# AEMLION-R4.net
KiCad netlist of a schematic drawn in EAGLE
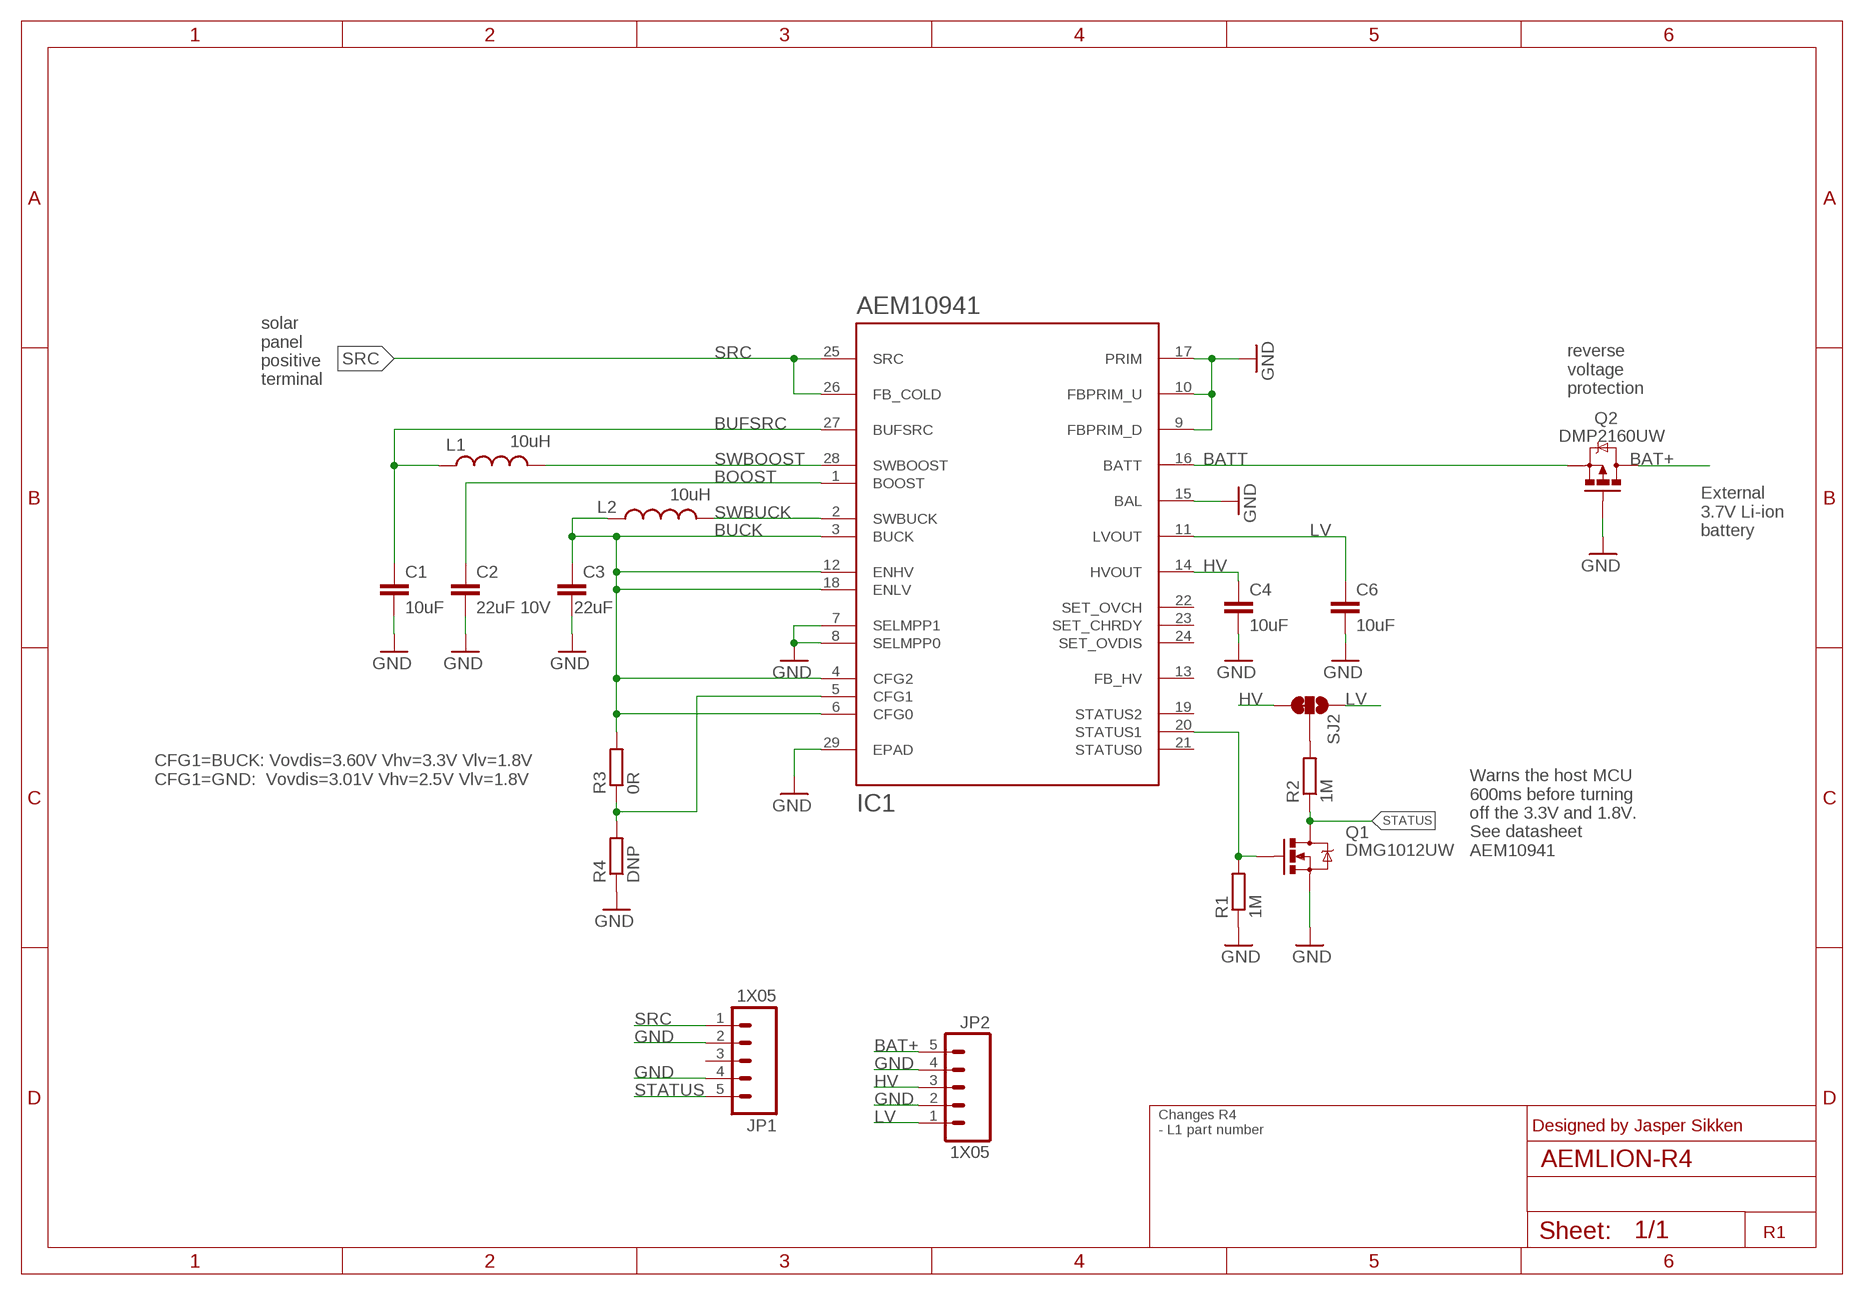
[diagram p0: schematic, sheet 1]

(export (version "E")
  (design (tool "Eeschema 10.0.6"))
  (components
    (comp (ref "C1")
      (value "10uF")
      (footprint "eagle-import:C0603")
      (fields
        (field (name "MF") "Taiyo Yuden")
        (field (name "MPN") "LMK107BBJ106MALT")
        (field (name "MF_1") "KEYSTONE")
        (field (name "MPN_1") "1049P")
      )
      (libsource (lib "eagle-import") (part "C0603_10UF"))
    )
    (comp (ref "C2")
      (value "22uF 10V")
      (footprint "eagle-import:C0603")
      (fields
        (field (name "MF") "Murata")
        (field (name "MPN") "GRM188R61A226ME15D")
        (field (name "MF_1") "TDK")
        (field (name "MPN_1") "CGA5L1X7S1A226M160AC")
      )
      (libsource (lib "eagle-import") (part "C0603_22UF"))
    )
    (comp (ref "C3")
      (value "22uF")
      (footprint "eagle-import:C0603")
      (fields
        (field (name "MF") "Taiyo Yuden")
        (field (name "MPN") "LMK107BBJ106MALT")
        (field (name "MF_1") "KEYSTONE")
        (field (name "MPN_1") "1049P")
      )
      (libsource (lib "eagle-import") (part "C0603_10UF"))
    )
    (comp (ref "C4")
      (value "10uF")
      (footprint "eagle-import:C0603")
      (fields
        (field (name "MF") "Taiyo Yuden")
        (field (name "MPN") "LMK107BBJ106MALT")
        (field (name "MF_1") "KEYSTONE")
        (field (name "MPN_1") "1049P")
      )
      (libsource (lib "eagle-import") (part "C0603_10UF"))
    )
    (comp (ref "C6")
      (value "10uF")
      (footprint "eagle-import:C0603")
      (fields
        (field (name "MF") "Taiyo Yuden")
        (field (name "MPN") "LMK107BBJ106MALT")
        (field (name "MF_1") "KEYSTONE")
        (field (name "MPN_1") "1049P")
      )
      (libsource (lib "eagle-import") (part "C0603_10UF"))
    )
    (comp (ref "IC1")
      (value "AEM10941")
      (footprint "eagle-import:QFN50P505X505X90-28")
      (fields (field (name "MF") "e-peas"))
      (libsource (lib "eagle-import") (part "AEM10941"))
    )
    (comp (ref "JP1")
      (value "1X05")
      (footprint "eagle-import:1X05_2.54MM_ROUND_NOSILK")
      (libsource (lib "eagle-import") (part "1X05"))
    )
    (comp (ref "JP2")
      (value "1X05")
      (footprint "eagle-import:1X05_2.54MM_ROUND_NOSILK")
      (libsource (lib "eagle-import") (part "1X05"))
    )
    (comp (ref "L1")
      (value "10uH")
      (footprint "eagle-import:L_3225MM")
      (fields (field (name "MF") "Murata") (field (name "MPN") "DFE322512F-100M=P2"))
      (libsource (lib "eagle-import") (part "L4"))
    )
    (comp (ref "L2")
      (value "10uH")
      (footprint "eagle-import:L0603")
      (fields
        (field (name "MF") "TDK")
        (field (name "MPN") "MLZ1608M100WT")
        (field (name "MF_1") "TAIYO YUDEN")
        (field (name "MPN_1") "CK2125100M-T")
      )
      (libsource (lib "eagle-import") (part "TSEM_L0603_10UH"))
    )
    (comp (ref "Q1")
      (value "DMG1012UW")
      (footprint "eagle-import:SOT323")
      (fields (field (name "MF") "Diodes") (field (name "MPN") "DMG1012UW-7"))
      (libsource (lib "eagle-import") (part "MOSFET-N-CHANNEL_DMG1012UW"))
    )
    (comp (ref "Q2")
      (value "DMP2160UW")
      (footprint "eagle-import:SOT323")
      (libsource (lib "eagle-import") (part "MOSFET-P-CHANNEL-DMP2160UW"))
    )
    (comp (ref "R1")
      (value "1M")
      (footprint "eagle-import:R0402")
      (fields (field (name "MF") "Walsin") (field (name "MPN") "WR04X1004FTL"))
      (libsource (lib "eagle-import") (part "R0402_1M"))
    )
    (comp (ref "R2")
      (value "1M")
      (footprint "eagle-import:R0402")
      (fields (field (name "MF") "Walsin") (field (name "MPN") "WR04X1004FTL"))
      (libsource (lib "eagle-import") (part "R0402_1M"))
    )
    (comp (ref "R3")
      (value "0R")
      (footprint "eagle-import:R0402")
      (fields (field (name "MF") "Walsin") (field (name "MPN") "WR04X1004FTL"))
      (libsource (lib "eagle-import") (part "R0402_1M"))
    )
    (comp (ref "R4")
      (value "DNP")
      (footprint "eagle-import:R0402")
      (fields (field (name "MF") "Walsin") (field (name "MPN") "WR04X1004FTL"))
      (libsource (lib "eagle-import") (part "R0402_1M"))
    )
    (comp (ref "SJ2")
      (value "SOLDERJUMPER_3WAY_12SHORT3WAY")
      (footprint "eagle-import:SJ_3S_NC_0402")
      (libsource (lib "eagle-import") (part "SOLDERJUMPER_3WAY_12SHORT3WAY"))
    )
  )
  (nets
    (net (code "1") (name "/BAT+") (class "Default")
      (node (ref "JP2") (pin "5") (pinfunction "5_5") (pintype "passive"))
      (node (ref "Q2") (pin "3") (pinfunction "D_3") (pintype "passive"))
    )
    (net (code "2") (name "/BATT") (class "Default")
      (node (ref "IC1") (pin "16") (pinfunction "BATT_16") (pintype "bidirectional"))
      (node (ref "Q2") (pin "2") (pinfunction "S_2") (pintype "passive"))
    )
    (net (code "3") (name "/BOOST") (class "Default")
      (node (ref "C2") (pin "1") (pinfunction "1_1") (pintype "passive"))
      (node (ref "IC1") (pin "1") (pinfunction "BOOST_1") (pintype "bidirectional"))
    )
    (net (code "4") (name "/BUCK") (class "Default")
      (node (ref "C3") (pin "1") (pinfunction "1_1") (pintype "passive"))
      (node (ref "IC1") (pin "12") (pinfunction "ENHV_12") (pintype "bidirectional"))
      (node (ref "IC1") (pin "18") (pinfunction "ENLV_18") (pintype "bidirectional"))
      (node (ref "IC1") (pin "3") (pinfunction "BUCK_3") (pintype "bidirectional"))
      (node (ref "IC1") (pin "4") (pinfunction "CFG2_4") (pintype "bidirectional"))
      (node (ref "IC1") (pin "6") (pinfunction "CFG0_6") (pintype "bidirectional"))
      (node (ref "L2") (pin "1") (pinfunction "1_1") (pintype "passive"))
      (node (ref "R3") (pin "2") (pinfunction "2_2") (pintype "passive"))
    )
    (net (code "5") (name "/BUFSRC") (class "Default")
      (node (ref "C1") (pin "1") (pinfunction "1_1") (pintype "passive"))
      (node (ref "IC1") (pin "27") (pinfunction "BUFSRC_27") (pintype "power_in"))
      (node (ref "L1") (pin "1") (pinfunction "1_1") (pintype "passive"))
    )
    (net (code "6") (name "/HV") (class "Default")
      (node (ref "C4") (pin "1") (pinfunction "1_1") (pintype "passive"))
      (node (ref "IC1") (pin "14") (pinfunction "HVOUT_14") (pintype "bidirectional"))
      (node (ref "JP2") (pin "3") (pinfunction "3_3") (pintype "passive"))
      (node (ref "SJ2") (pin "1") (pinfunction "1_1") (pintype "passive"))
    )
    (net (code "7") (name "/LV") (class "Default")
      (node (ref "C6") (pin "1") (pinfunction "1_1") (pintype "passive"))
      (node (ref "IC1") (pin "11") (pinfunction "LVOUT_11") (pintype "bidirectional"))
      (node (ref "JP2") (pin "1") (pinfunction "1_1") (pintype "passive"))
      (node (ref "SJ2") (pin "3") (pinfunction "3_3") (pintype "passive"))
    )
    (net (code "8") (name "/SWBOOST") (class "Default")
      (node (ref "IC1") (pin "28") (pinfunction "SWBOOST_28") (pintype "power_in"))
      (node (ref "L1") (pin "2") (pinfunction "2_2") (pintype "passive"))
    )
    (net (code "9") (name "/SWBUCK") (class "Default")
      (node (ref "IC1") (pin "2") (pinfunction "SWBUCK_2") (pintype "bidirectional"))
      (node (ref "L2") (pin "2") (pinfunction "2_2") (pintype "passive"))
    )
    (net (code "10") (name "GND") (class "Default")
      (node (ref "C1") (pin "2") (pinfunction "2_2") (pintype "passive"))
      (node (ref "C2") (pin "2") (pinfunction "2_2") (pintype "passive"))
      (node (ref "C3") (pin "2") (pinfunction "2_2") (pintype "passive"))
      (node (ref "C4") (pin "2") (pinfunction "2_2") (pintype "passive"))
      (node (ref "C6") (pin "2") (pinfunction "2_2") (pintype "passive"))
      (node (ref "IC1") (pin "10") (pinfunction "FBPRIM_U_10") (pintype "bidirectional"))
      (node (ref "IC1") (pin "15") (pinfunction "BAL_15") (pintype "bidirectional"))
      (node (ref "IC1") (pin "17") (pinfunction "PRIM_17") (pintype "bidirectional"))
      (node (ref "IC1") (pin "29") (pinfunction "EPAD_29") (pintype "power_in"))
      (node (ref "IC1") (pin "7") (pinfunction "SELMPP1_7") (pintype "bidirectional"))
      (node (ref "IC1") (pin "8") (pinfunction "SELMPP0_8") (pintype "bidirectional"))
      (node (ref "IC1") (pin "9") (pinfunction "FBPRIM_D_9") (pintype "bidirectional"))
      (node (ref "JP1") (pin "2") (pinfunction "2_2") (pintype "passive"))
      (node (ref "JP1") (pin "4") (pinfunction "4_4") (pintype "passive"))
      (node (ref "JP2") (pin "2") (pinfunction "2_2") (pintype "passive"))
      (node (ref "JP2") (pin "4") (pinfunction "4_4") (pintype "passive"))
      (node (ref "Q1") (pin "2") (pinfunction "S_2") (pintype "passive"))
      (node (ref "Q2") (pin "1") (pinfunction "G_1") (pintype "passive"))
      (node (ref "R1") (pin "1") (pinfunction "1_1") (pintype "passive"))
      (node (ref "R4") (pin "1") (pinfunction "1_1") (pintype "passive"))
    )
    (net (code "11") (name "Net-(IC1-CFG1)") (class "Default")
      (node (ref "IC1") (pin "5") (pinfunction "CFG1_5") (pintype "bidirectional"))
      (node (ref "R3") (pin "1") (pinfunction "1_1") (pintype "passive"))
      (node (ref "R4") (pin "2") (pinfunction "2_2") (pintype "passive"))
    )
    (net (code "12") (name "Net-(IC1-STATUS1)") (class "Default")
      (node (ref "IC1") (pin "20") (pinfunction "STATUS1_20") (pintype "bidirectional"))
      (node (ref "Q1") (pin "1") (pinfunction "G_1") (pintype "passive"))
      (node (ref "R1") (pin "2") (pinfunction "2_2") (pintype "passive"))
    )
    (net (code "13") (name "Net-(R2-Pad2)") (class "Default")
      (node (ref "R2") (pin "2") (pinfunction "2_2") (pintype "passive"))
      (node (ref "SJ2") (pin "2") (pinfunction "2_2") (pintype "passive"))
    )
    (net (code "14") (name "SRC") (class "Default")
      (node (ref "IC1") (pin "25") (pinfunction "SRC_25") (pintype "power_in"))
      (node (ref "IC1") (pin "26") (pinfunction "FB_COLD_26") (pintype "input"))
      (node (ref "JP1") (pin "1") (pinfunction "1_1") (pintype "passive"))
    )
    (net (code "15") (name "STATUS") (class "Default")
      (node (ref "JP1") (pin "5") (pinfunction "5_5") (pintype "passive"))
      (node (ref "Q1") (pin "3") (pinfunction "D_3") (pintype "passive"))
      (node (ref "R2") (pin "1") (pinfunction "1_1") (pintype "passive"))
    )
    (net (code "16") (name "unconnected-(IC1-FB_HV-Pad13)") (class "Default")
      (node (ref "IC1") (pin "13") (pinfunction "FB_HV_13") (pintype "bidirectional"))
    )
    (net (code "17") (name "unconnected-(IC1-SET_CHRDY-Pad23)") (class "Default")
      (node (ref "IC1") (pin "23") (pinfunction "SET_CHRDY_23") (pintype "bidirectional"))
    )
    (net (code "18") (name "unconnected-(IC1-SET_OVCH-Pad22)") (class "Default")
      (node (ref "IC1") (pin "22") (pinfunction "SET_OVCH_22") (pintype "bidirectional"))
    )
    (net (code "19") (name "unconnected-(IC1-SET_OVDIS-Pad24)") (class "Default")
      (node (ref "IC1") (pin "24") (pinfunction "SET_OVDIS_24") (pintype "bidirectional"))
    )
    (net (code "20") (name "unconnected-(IC1-STATUS0-Pad21)") (class "Default")
      (node (ref "IC1") (pin "21") (pinfunction "STATUS0_21") (pintype "bidirectional"))
    )
    (net (code "21") (name "unconnected-(IC1-STATUS2-Pad19)") (class "Default")
      (node (ref "IC1") (pin "19") (pinfunction "STATUS2_19") (pintype "bidirectional"))
    )
    (net (code "22") (name "unconnected-(JP1-Pad3)") (class "Default")
      (node (ref "JP1") (pin "3") (pinfunction "3_3") (pintype "passive"))
    )
  )
)
